# 09_CAN.net
KiCad netlist of a schematic drawn in Altium Designer
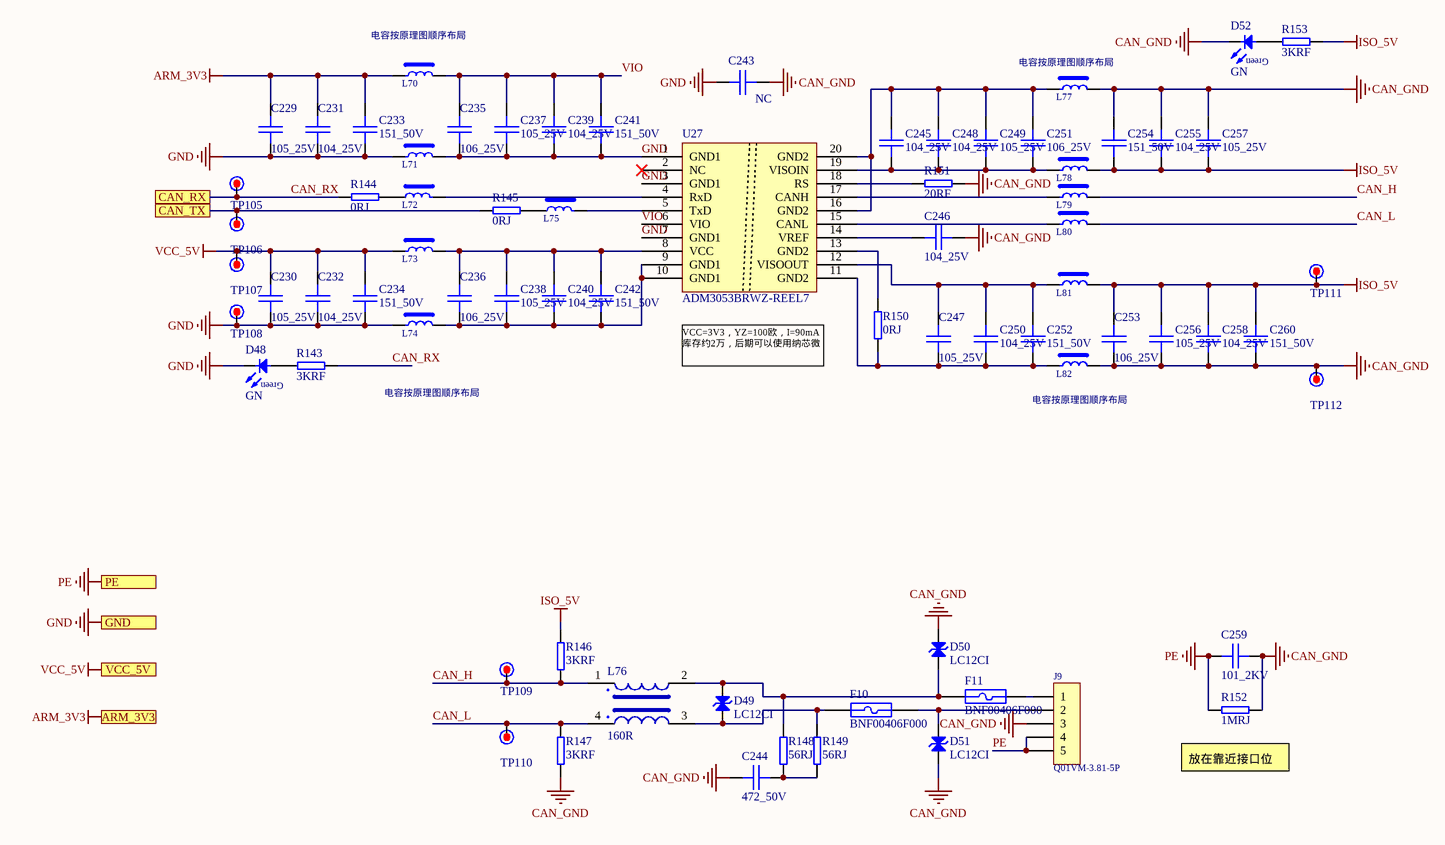
[diagram p0: 09_CAN.SchDoc]

(export (version "E")
  (design (tool "Eeschema 10.0.6"))
  (components
    (comp (ref "C229")
      (value "105_25V")
      (footprint "0603C")
      (description "贴片电容1uF25VX7R125℃K0603")
      (fields (field (name "检查人") "江应平"))
      (libsource (lib "NE Layout Library") (part "贴片电容1uF25VX7R125℃K0603"))
    )
    (comp (ref "C230")
      (value "105_25V")
      (footprint "0603C")
      (description "贴片电容1uF25VX7R125℃K0603")
      (fields (field (name "检查人") "江应平"))
      (libsource (lib "NE Layout Library") (part "贴片电容1uF25VX7R125℃K0603"))
    )
    (comp (ref "C231")
      (value "104_25V")
      (footprint "0402C")
      (description "贴片电容100nF25VX7R125℃K0402")
      (fields (field (name "检查人") "江应平"))
      (libsource (lib "NE Layout Library") (part "贴片电容100nF25VX7R125℃K0402"))
    )
    (comp (ref "C232")
      (value "104_25V")
      (footprint "0402C")
      (description "贴片电容100nF25VX7R125℃K0402")
      (fields (field (name "检查人") "江应平"))
      (libsource (lib "NE Layout Library") (part "贴片电容100nF25VX7R125℃K0402"))
    )
    (comp (ref "C233")
      (value "151_50V")
      (footprint "0603C")
      (description "贴片电容150pF50VCOG125℃K0603")
      (fields (field (name "检查人") "江应平"))
      (libsource (lib "NE Layout Library") (part "1102010037"))
    )
    (comp (ref "C234")
      (value "151_50V")
      (footprint "0603C")
      (description "贴片电容150pF50VCOG125℃K0603")
      (fields (field (name "检查人") "江应平"))
      (libsource (lib "NE Layout Library") (part "1102010037"))
    )
    (comp (ref "C235")
      (value "106_25V")
      (footprint "0805C")
      (description "贴片电容10uF25VX7R125℃K0805")
      (fields (field (name "检查人") "江应平"))
      (libsource (lib "NE Layout Library") (part "贴片电容10uF25VX7R125℃K0805"))
    )
    (comp (ref "C236")
      (value "106_25V")
      (footprint "0805C")
      (description "贴片电容10uF25VX7R125℃K0805")
      (fields (field (name "检查人") "江应平"))
      (libsource (lib "NE Layout Library") (part "贴片电容10uF25VX7R125℃K0805"))
    )
    (comp (ref "C237")
      (value "105_25V")
      (footprint "0603C")
      (description "贴片电容1uF25VX7R125℃K0603")
      (fields (field (name "检查人") "江应平"))
      (libsource (lib "NE Layout Library") (part "贴片电容1uF25VX7R125℃K0603"))
    )
    (comp (ref "C238")
      (value "105_25V")
      (footprint "0603C")
      (description "贴片电容1uF25VX7R125℃K0603")
      (fields (field (name "检查人") "江应平"))
      (libsource (lib "NE Layout Library") (part "贴片电容1uF25VX7R125℃K0603"))
    )
    (comp (ref "C239")
      (value "104_25V")
      (footprint "0603C")
      (description "贴片电容100nF25VX7R125℃K0603")
      (fields (field (name "检查人") "江应平"))
      (libsource (lib "NE Layout Library") (part "1102010026"))
    )
    (comp (ref "C240")
      (value "104_25V")
      (footprint "0603C")
      (description "贴片电容100nF25VX7R125℃K0603")
      (fields (field (name "检查人") "江应平"))
      (libsource (lib "NE Layout Library") (part "1102010026"))
    )
    (comp (ref "C241")
      (value "151_50V")
      (footprint "0603C")
      (description "贴片电容150pF50VCOG125℃K0603")
      (fields (field (name "检查人") "江应平"))
      (libsource (lib "NE Layout Library") (part "1102010037"))
    )
    (comp (ref "C242")
      (value "151_50V")
      (footprint "0603C")
      (description "贴片电容150pF50VCOG125℃K0603")
      (fields (field (name "检查人") "江应平"))
      (libsource (lib "NE Layout Library") (part "1102010037"))
    )
    (comp (ref "C243")
      (value "NC")
      (footprint "SMDC_L11.4W6H2.5")
      (libsource (lib "NE BufferLibrary0616") (part "电容DK1E3EA102M86RAH01"))
    )
    (comp (ref "C244")
      (value "472_50V")
      (footprint "0603C")
      (description "贴片电容4.7nF50VX7R125℃K0603")
      (fields (field (name "检查人") "江应平"))
      (libsource (lib "NE Layout Library") (part "1102010080"))
    )
    (comp (ref "C245")
      (value "104_25V")
      (footprint "0603C")
      (description "贴片电容100nF25VX7R125℃K0603")
      (fields (field (name "检查人") "江应平"))
      (libsource (lib "NE Layout Library") (part "1102010026"))
    )
    (comp (ref "C246")
      (value "104_25V")
      (footprint "0603C")
      (description "贴片电容100nF25VX7R125℃K0603")
      (fields (field (name "检查人") "江应平"))
      (libsource (lib "NE Layout Library") (part "1102010026"))
    )
    (comp (ref "C247")
      (value "105_25V")
      (footprint "0603C")
      (description "贴片电容1uF25VX7R125℃K0603")
      (fields (field (name "检查人") "江应平"))
      (libsource (lib "NE Layout Library") (part "贴片电容1uF25VX7R125℃K0603"))
    )
    (comp (ref "C248")
      (value "104_25V")
      (footprint "0603C")
      (description "贴片电容100nF25VX7R125℃K0603")
      (fields (field (name "检查人") "江应平"))
      (libsource (lib "NE Layout Library") (part "1102010026"))
    )
    (comp (ref "C249")
      (value "105_25V")
      (footprint "0603C")
      (description "贴片电容1uF25VX7R125℃K0603")
      (fields (field (name "检查人") "江应平"))
      (libsource (lib "NE Layout Library") (part "贴片电容1uF25VX7R125℃K0603"))
    )
    (comp (ref "C250")
      (value "104_25V")
      (footprint "0603C")
      (description "贴片电容100nF25VX7R125℃K0603")
      (fields (field (name "检查人") "江应平"))
      (libsource (lib "NE Layout Library") (part "1102010026"))
    )
    (comp (ref "C251")
      (value "106_25V")
      (footprint "0805C")
      (description "贴片电容10uF25VX7R125℃K0805")
      (fields (field (name "检查人") "江应平"))
      (libsource (lib "NE Layout Library") (part "贴片电容10uF25VX7R125℃K0805"))
    )
    (comp (ref "C252")
      (value "151_50V")
      (footprint "0603C")
      (description "贴片电容150pF50VCOG125℃K0603")
      (fields (field (name "检查人") "江应平"))
      (libsource (lib "NE Layout Library") (part "1102010037"))
    )
    (comp (ref "C253")
      (value "106_25V")
      (footprint "0805C")
      (description "贴片电容10uF25VX7R125℃K0805")
      (fields (field (name "检查人") "江应平"))
      (libsource (lib "NE Layout Library") (part "贴片电容10uF25VX7R125℃K0805"))
    )
    (comp (ref "C254")
      (value "151_50V")
      (footprint "0603C")
      (description "贴片电容150pF50VCOG125℃K0603")
      (fields (field (name "检查人") "江应平"))
      (libsource (lib "NE Layout Library") (part "1102010037"))
    )
    (comp (ref "C255")
      (value "104_25V")
      (footprint "0603C")
      (description "贴片电容100nF25VX7R125℃K0603")
      (fields (field (name "检查人") "江应平"))
      (libsource (lib "NE Layout Library") (part "1102010026"))
    )
    (comp (ref "C256")
      (value "105_25V")
      (footprint "0603C")
      (description "贴片电容1uF25VX7R125℃K0603")
      (fields (field (name "检查人") "江应平"))
      (libsource (lib "NE Layout Library") (part "贴片电容1uF25VX7R125℃K0603"))
    )
    (comp (ref "C257")
      (value "105_25V")
      (footprint "0603C")
      (description "贴片电容1uF25VX7R125℃K0603")
      (fields (field (name "检查人") "江应平"))
      (libsource (lib "NE Layout Library") (part "贴片电容1uF25VX7R125℃K0603"))
    )
    (comp (ref "C258")
      (value "104_25V")
      (footprint "0603C")
      (description "贴片电容100nF25VX7R125℃K0603")
      (fields (field (name "检查人") "江应平"))
      (libsource (lib "NE Layout Library") (part "1102010026"))
    )
    (comp (ref "C259")
      (value "101_2KV")
      (footprint "1812C")
      (description "贴片电容100pF2000VNPO125℃K1812")
      (fields (field (name "检查人") "江应平"))
      (libsource (lib "NE Layout Library") (part "1102010145"))
    )
    (comp (ref "C260")
      (value "151_50V")
      (footprint "0603C")
      (description "贴片电容150pF50VCOG125℃K0603")
      (fields (field (name "检查人") "江应平"))
      (libsource (lib "NE Layout Library") (part "1102010037"))
    )
    (comp (ref "D48")
      (value "GN")
      (footprint "SMDD_0603G")
      (description "贴片发光二极管GN0603")
      (fields (field (name "检查人") "江应平"))
      (libsource (lib "NE Layout Library") (part "贴片发光二极管GN0603"))
    )
    (comp (ref "D49")
      (value "LC12CI")
      (footprint "SMDD_SOD323(无极性)")
      (libsource (lib "NE BufferLibrary0916") (part "瞬态抑制二极管(TVS)LC12CI"))
    )
    (comp (ref "D50")
      (value "LC12CI")
      (footprint "SMDD_SOD323(无极性)")
      (libsource (lib "NE BufferLibrary0916") (part "瞬态抑制二极管(TVS)LC12CI"))
    )
    (comp (ref "D51")
      (value "LC12CI")
      (footprint "SMDD_SOD323(无极性)")
      (libsource (lib "NE BufferLibrary0916") (part "瞬态抑制二极管(TVS)LC12CI"))
    )
    (comp (ref "D52")
      (value "GN")
      (footprint "SMDD_0603G")
      (description "贴片发光二极管GN0603")
      (fields (field (name "检查人") "江应平"))
      (libsource (lib "NE Layout Library") (part "贴片发光二极管GN0603"))
    )
    (comp (ref "F10")
      (value "BNF00406F000")
      (footprint "SMDF_0603")
      (description "自恢复保险丝BNF00406F0000603")
      (fields (field (name "检查人") "江应平"))
      (libsource (lib "NE Layout Library") (part "1115000150"))
    )
    (comp (ref "F11")
      (value "BNF00406F000")
      (footprint "SMDF_0603")
      (description "自恢复保险丝BNF00406F0000603")
      (fields (field (name "检查人") "江应平"))
      (libsource (lib "NE Layout Library") (part "1115000150"))
    )
    (comp (ref "J9")
      (value "Q01VM-3.81-5P")
      (footprint "DIPJS_Q01VM_S3.81R0.8_5P")
      (description "连接座Q01VM-3.81-5P250V7A")
      (libsource (lib "NE Layout Library") (part "1214020289"))
    )
    (comp (ref "L70")
      (value "1.8K")
      (footprint "0402L")
      (description "贴片磁珠1.8K200mA100MHzL0402")
      (fields (field (name "检查人") "江应平"))
      (libsource (lib "NE Layout Library") (part "1111100012"))
    )
    (comp (ref "L71")
      (value "1.8K")
      (footprint "0402L")
      (description "贴片磁珠1.8K200mA100MHzL0402")
      (fields (field (name "检查人") "江应平"))
      (libsource (lib "NE Layout Library") (part "1111100012"))
    )
    (comp (ref "L72")
      (value "1.8K")
      (footprint "0402L")
      (description "贴片磁珠1.8K200mA100MHzL0402")
      (fields (field (name "检查人") "江应平"))
      (libsource (lib "") (part "1111100012_1"))
    )
    (comp (ref "L73")
      (value "1.8K")
      (footprint "0402L")
      (description "贴片磁珠1.8K200mA100MHzL0402")
      (fields (field (name "检查人") "江应平"))
      (libsource (lib "NE Layout Library") (part "1111100012"))
    )
    (comp (ref "L74")
      (value "1.8K")
      (footprint "0402L")
      (description "贴片磁珠1.8K200mA100MHzL0402")
      (fields (field (name "检查人") "江应平"))
      (libsource (lib "NE Layout Library") (part "1111100012"))
    )
    (comp (ref "L75")
      (value "1.8K")
      (footprint "0402L")
      (description "贴片磁珠1.8K200mA100MHzL0402")
      (fields (field (name "检查人") "江应平"))
      (libsource (lib "") (part "1111100012_1"))
    )
    (comp (ref "L76")
      (value "160R")
      (footprint "SMDL_L3.2W1.6_H1.8")
      (description "贴片共模电感160R0.34A125V1MHzSMD1206")
      (fields (field (name "检查人") "江应平"))
      (libsource (lib "NE Layout Library") (part "1111010051"))
    )
    (comp (ref "L77")
      (value "1.8K")
      (footprint "0402L")
      (description "贴片磁珠1.8K200mA100MHzL0402")
      (fields (field (name "检查人") "江应平"))
      (libsource (lib "NE Layout Library") (part "1111100012"))
    )
    (comp (ref "L78")
      (value "1.8K")
      (footprint "0402L")
      (description "贴片磁珠1.8K200mA100MHzL0402")
      (fields (field (name "检查人") "江应平"))
      (libsource (lib "NE Layout Library") (part "1111100012"))
    )
    (comp (ref "L79")
      (value "1.8K")
      (footprint "0402L")
      (description "贴片磁珠1.8K200mA100MHzL0402")
      (fields (field (name "检查人") "江应平"))
      (libsource (lib "NE Layout Library") (part "1111100012"))
    )
    (comp (ref "L80")
      (value "1.8K")
      (footprint "0402L")
      (description "贴片磁珠1.8K200mA100MHzL0402")
      (fields (field (name "检查人") "江应平"))
      (libsource (lib "NE Layout Library") (part "1111100012"))
    )
    (comp (ref "L81")
      (value "1.8K")
      (footprint "0402L")
      (description "贴片磁珠1.8K200mA100MHzL0402")
      (fields (field (name "检查人") "江应平"))
      (libsource (lib "NE Layout Library") (part "1111100012"))
    )
    (comp (ref "L82")
      (value "1.8K")
      (footprint "0402L")
      (description "贴片磁珠1.8K200mA100MHzL0402")
      (fields (field (name "检查人") "江应平"))
      (libsource (lib "NE Layout Library") (part "1111100012"))
    )
    (comp (ref "R143")
      (value "3KRF")
      (footprint "0603R")
      (description "贴片电阻3KRF0.1W100ppm0603")
      (fields (field (name "检查人") "江应平"))
      (libsource (lib "NE Layout Library") (part "贴片电阻3KRF0.1W100ppm0603"))
    )
    (comp (ref "R144")
      (value "0RJ")
      (footprint "0402R")
      (description "贴片电阻0RJ0.0625W100ppm0402")
      (fields (field (name "检查人") "江应平"))
      (libsource (lib "NE Layout Library") (part "1101010535"))
    )
    (comp (ref "R145")
      (value "0RJ")
      (footprint "0402R")
      (description "贴片电阻0RJ0.0625W100ppm0402")
      (fields (field (name "检查人") "江应平"))
      (libsource (lib "NE Layout Library") (part "1101010535"))
    )
    (comp (ref "R146")
      (value "3KRF")
      (footprint "0603R")
      (description "贴片电阻3KRF0.1W100ppm0603")
      (fields (field (name "检查人") "江应平"))
      (libsource (lib "NE Layout Library") (part "1101010254"))
    )
    (comp (ref "R147")
      (value "3KRF")
      (footprint "0603R")
      (description "贴片电阻3KRF0.1W100ppm0603")
      (fields (field (name "检查人") "江应平"))
      (libsource (lib "NE Layout Library") (part "1101010254"))
    )
    (comp (ref "R148")
      (value "56RJ")
      (footprint "0805R")
      (description "贴片电阻56RJ0.125W100ppm0805")
      (fields (field (name "检查人") "江应平"))
      (libsource (lib "NE Layout Library") (part "1101010179"))
    )
    (comp (ref "R149")
      (value "56RJ")
      (footprint "0805R")
      (description "贴片电阻56RJ0.125W100ppm0805")
      (fields (field (name "检查人") "江应平"))
      (libsource (lib "NE Layout Library") (part "1101010179"))
    )
    (comp (ref "R150")
      (value "0RJ")
      (footprint "0603R")
      (description "贴片电阻0RJ0.1W0603")
      (fields (field (name "检查人") "江应平"))
      (libsource (lib "NE Layout Library") (part "1101010220"))
    )
    (comp (ref "R151")
      (value "20RF")
      (footprint "0603R")
      (description "贴片电阻20RF0.1W100ppm0603")
      (fields (field (name "检查人") "江应平"))
      (libsource (lib "NE Layout Library") (part "1101010274"))
    )
    (comp (ref "R152")
      (value "1MRJ")
      (footprint "2512R")
      (description "贴片电阻1MRJ1W100ppm2512")
      (fields (field (name "检查人") "江应平"))
      (libsource (lib "NE Layout Library") (part "1101010313"))
    )
    (comp (ref "R153")
      (value "3KRF")
      (footprint "0603R")
      (description "贴片电阻3KRF0.1W100ppm0603")
      (fields (field (name "检查人") "江应平"))
      (libsource (lib "NE Layout Library") (part "贴片电阻3KRF0.1W100ppm0603"))
    )
    (comp (ref "TP105")
      (value "TP")
      (footprint "TP-1.0mm")
      (description "通用测试点")
      (libsource (lib "NE Layout Library") (part "TP"))
    )
    (comp (ref "TP106")
      (value "TP")
      (footprint "TP-1.0mm")
      (description "通用测试点")
      (libsource (lib "NE Layout Library") (part "TP"))
    )
    (comp (ref "TP107")
      (value "TP")
      (footprint "TP-1.0mm")
      (description "通用测试点")
      (libsource (lib "NE Layout Library") (part "TP"))
    )
    (comp (ref "TP108")
      (value "TP")
      (footprint "TP-1.0mm")
      (description "通用测试点")
      (libsource (lib "NE Layout Library") (part "TP"))
    )
    (comp (ref "TP109")
      (value "TP")
      (footprint "TP-1.0mm")
      (description "通用测试点")
      (libsource (lib "NE Layout Library") (part "TP"))
    )
    (comp (ref "TP110")
      (value "TP")
      (footprint "TP-1.0mm")
      (description "通用测试点")
      (libsource (lib "NE Layout Library") (part "TP"))
    )
    (comp (ref "TP111")
      (value "TP")
      (footprint "TP-1.0mm")
      (description "通用测试点")
      (libsource (lib "NE Layout Library") (part "TP"))
    )
    (comp (ref "TP112")
      (value "TP")
      (footprint "TP-1.0mm")
      (description "通用测试点")
      (libsource (lib "NE Layout Library") (part "TP"))
    )
    (comp (ref "U27")
      (value "ADM3053BRWZ-REEL7")
      (footprint "SMDU_SOP20-L_S1.27X10")
      (description "隔离通信芯片ADM3053BRWZ-REEL7RW-20")
      (fields (field (name "检查人") "江应平"))
      (libsource (lib "NE Layout Library") (part "1110080014"))
    )
  )
  (nets
    (net (code "1") (name "/CAN_H") (class "Default")
      (node (ref "L76") (pin "1") (pinfunction "1_1") (pintype "passive"))
      (node (ref "L79") (pin "1") (pinfunction "1_1") (pintype "passive"))
      (node (ref "R146") (pin "1") (pinfunction "1_1") (pintype "passive"))
      (node (ref "TP109") (pin "1") (pinfunction "1_1") (pintype "passive"))
    )
    (net (code "2") (name "/CAN_L") (class "Default")
      (node (ref "L76") (pin "4") (pinfunction "4_4") (pintype "passive"))
      (node (ref "L80") (pin "1") (pinfunction "1_1") (pintype "passive"))
      (node (ref "R147") (pin "2") (pinfunction "2_2") (pintype "passive"))
      (node (ref "TP110") (pin "1") (pinfunction "1_1") (pintype "passive"))
    )
    (net (code "3") (name "/CAN_RX") (class "Default")
      (node (ref "R143") (pin "1") (pinfunction "1_1") (pintype "passive"))
      (node (ref "R144") (pin "2") (pinfunction "2_2") (pintype "passive"))
      (node (ref "TP105") (pin "1") (pinfunction "1_1") (pintype "passive"))
    )
    (net (code "4") (name "/CAN_TX") (class "Default")
      (node (ref "R145") (pin "2") (pinfunction "2_2") (pintype "passive"))
      (node (ref "TP106") (pin "1") (pinfunction "1_1") (pintype "passive"))
    )
    (net (code "5") (name "/VIO") (class "Default")
      (node (ref "C235") (pin "1") (pinfunction "1_1") (pintype "passive"))
      (node (ref "C237") (pin "1") (pinfunction "1_1") (pintype "passive"))
      (node (ref "C239") (pin "1") (pinfunction "1_1") (pintype "passive"))
      (node (ref "C241") (pin "1") (pinfunction "1_1") (pintype "passive"))
      (node (ref "L70") (pin "1") (pinfunction "1_1") (pintype "passive"))
      (node (ref "U27") (pin "6") (pinfunction "VIO_6") (pintype "passive"))
    )
    (net (code "6") (name "ARM_3V3") (class "Default")
      (node (ref "C229") (pin "1") (pinfunction "1_1") (pintype "passive"))
      (node (ref "C231") (pin "1") (pinfunction "1_1") (pintype "passive"))
      (node (ref "C233") (pin "1") (pinfunction "1_1") (pintype "passive"))
      (node (ref "L70") (pin "2") (pinfunction "2_2") (pintype "passive"))
    )
    (net (code "7") (name "CAN_GND") (class "Default")
      (node (ref "C243") (pin "2") (pinfunction "2_2") (pintype "passive"))
      (node (ref "C244") (pin "1") (pinfunction "1_1") (pintype "passive"))
      (node (ref "C246") (pin "2") (pinfunction "2_2") (pintype "passive"))
      (node (ref "C253") (pin "2") (pinfunction "2_2") (pintype "passive"))
      (node (ref "C254") (pin "1") (pinfunction "1_1") (pintype "passive"))
      (node (ref "C255") (pin "1") (pinfunction "1_1") (pintype "passive"))
      (node (ref "C256") (pin "2") (pinfunction "2_2") (pintype "passive"))
      (node (ref "C257") (pin "1") (pinfunction "1_1") (pintype "passive"))
      (node (ref "C258") (pin "2") (pinfunction "2_2") (pintype "passive"))
      (node (ref "C259") (pin "2") (pinfunction "2_2") (pintype "passive"))
      (node (ref "C260") (pin "2") (pinfunction "2_2") (pintype "passive"))
      (node (ref "D50") (pin "2") (pinfunction "Pin2_2") (pintype "passive"))
      (node (ref "D51") (pin "1") (pinfunction "Pin1_1") (pintype "passive"))
      (node (ref "D52") (pin "2") (pinfunction "K_2") (pintype "passive"))
      (node (ref "J9") (pin "3") (pinfunction "3_3") (pintype "passive"))
      (node (ref "L77") (pin "1") (pinfunction "1_1") (pintype "passive"))
      (node (ref "L82") (pin "1") (pinfunction "1_1") (pintype "passive"))
      (node (ref "R147") (pin "1") (pinfunction "1_1") (pintype "passive"))
      (node (ref "R151") (pin "2") (pinfunction "2_2") (pintype "passive"))
      (node (ref "R152") (pin "2") (pinfunction "2_2") (pintype "passive"))
      (node (ref "TP112") (pin "1") (pinfunction "1_1") (pintype "passive"))
    )
    (net (code "8") (name "GND") (class "Default")
      (node (ref "C229") (pin "2") (pinfunction "2_2") (pintype "passive"))
      (node (ref "C230") (pin "2") (pinfunction "2_2") (pintype "passive"))
      (node (ref "C231") (pin "2") (pinfunction "2_2") (pintype "passive"))
      (node (ref "C232") (pin "2") (pinfunction "2_2") (pintype "passive"))
      (node (ref "C233") (pin "2") (pinfunction "2_2") (pintype "passive"))
      (node (ref "C234") (pin "2") (pinfunction "2_2") (pintype "passive"))
      (node (ref "C235") (pin "2") (pinfunction "2_2") (pintype "passive"))
      (node (ref "C237") (pin "2") (pinfunction "2_2") (pintype "passive"))
      (node (ref "C239") (pin "2") (pinfunction "2_2") (pintype "passive"))
      (node (ref "C241") (pin "2") (pinfunction "2_2") (pintype "passive"))
      (node (ref "C243") (pin "1") (pinfunction "1_1") (pintype "passive"))
      (node (ref "D48") (pin "2") (pinfunction "K_2") (pintype "passive"))
      (node (ref "L71") (pin "1") (pinfunction "1_1") (pintype "passive"))
      (node (ref "L71") (pin "2") (pinfunction "2_2") (pintype "passive"))
      (node (ref "L74") (pin "2") (pinfunction "2_2") (pintype "passive"))
      (node (ref "TP108") (pin "1") (pinfunction "1_1") (pintype "passive"))
      (node (ref "U27") (pin "1") (pinfunction "GND1_1") (pintype "passive"))
      (node (ref "U27") (pin "3") (pinfunction "GND1_3") (pintype "passive"))
      (node (ref "U27") (pin "7") (pinfunction "GND1_7") (pintype "passive"))
    )
    (net (code "9") (name "ISO_5V") (class "Default")
      (node (ref "C253") (pin "1") (pinfunction "1_1") (pintype "passive"))
      (node (ref "C254") (pin "2") (pinfunction "2_2") (pintype "passive"))
      (node (ref "C255") (pin "2") (pinfunction "2_2") (pintype "passive"))
      (node (ref "C256") (pin "1") (pinfunction "1_1") (pintype "passive"))
      (node (ref "C257") (pin "2") (pinfunction "2_2") (pintype "passive"))
      (node (ref "C258") (pin "1") (pinfunction "1_1") (pintype "passive"))
      (node (ref "C260") (pin "1") (pinfunction "1_1") (pintype "passive"))
      (node (ref "L78") (pin "1") (pinfunction "1_1") (pintype "passive"))
      (node (ref "L81") (pin "1") (pinfunction "1_1") (pintype "passive"))
      (node (ref "R146") (pin "2") (pinfunction "2_2") (pintype "passive"))
      (node (ref "R153") (pin "1") (pinfunction "1_1") (pintype "passive"))
      (node (ref "TP111") (pin "1") (pinfunction "1_1") (pintype "passive"))
    )
    (net (code "10") (name "Net-(C236-Pad2)") (class "Default")
      (node (ref "C236") (pin "2") (pinfunction "2_2") (pintype "passive"))
      (node (ref "C238") (pin "2") (pinfunction "2_2") (pintype "passive"))
      (node (ref "C240") (pin "2") (pinfunction "2_2") (pintype "passive"))
      (node (ref "C242") (pin "2") (pinfunction "2_2") (pintype "passive"))
      (node (ref "L74") (pin "1") (pinfunction "1_1") (pintype "passive"))
      (node (ref "U27") (pin "10") (pinfunction "GND1_10") (pintype "passive"))
      (node (ref "U27") (pin "9") (pinfunction "GND1_9") (pintype "passive"))
    )
    (net (code "11") (name "Net-(C244-Pad2)") (class "Default")
      (node (ref "C244") (pin "2") (pinfunction "2_2") (pintype "passive"))
      (node (ref "R148") (pin "1") (pinfunction "1_1") (pintype "passive"))
      (node (ref "R149") (pin "1") (pinfunction "1_1") (pintype "passive"))
    )
    (net (code "12") (name "Net-(C245-Pad1)") (class "Default")
      (node (ref "C245") (pin "1") (pinfunction "1_1") (pintype "passive"))
      (node (ref "C248") (pin "1") (pinfunction "1_1") (pintype "passive"))
      (node (ref "C249") (pin "1") (pinfunction "1_1") (pintype "passive"))
      (node (ref "C251") (pin "1") (pinfunction "1_1") (pintype "passive"))
      (node (ref "L77") (pin "2") (pinfunction "2_2") (pintype "passive"))
      (node (ref "U27") (pin "16") (pinfunction "GND2_16") (pintype "passive"))
      (node (ref "U27") (pin "20") (pinfunction "GND2_20") (pintype "passive"))
    )
    (net (code "13") (name "Net-(C247-Pad2)") (class "Default")
      (node (ref "C247") (pin "2") (pinfunction "2_2") (pintype "passive"))
      (node (ref "C250") (pin "2") (pinfunction "2_2") (pintype "passive"))
      (node (ref "C252") (pin "2") (pinfunction "2_2") (pintype "passive"))
      (node (ref "L82") (pin "2") (pinfunction "2_2") (pintype "passive"))
      (node (ref "R150") (pin "1") (pinfunction "1_1") (pintype "passive"))
      (node (ref "U27") (pin "11") (pinfunction "GND2_11") (pintype "passive"))
    )
    (net (code "14") (name "Net-(D48-A)") (class "Default")
      (node (ref "D48") (pin "1") (pinfunction "A_1") (pintype "passive"))
      (node (ref "R143") (pin "2") (pinfunction "2_2") (pintype "passive"))
    )
    (net (code "15") (name "Net-(D49-Pin1)") (class "Default")
      (node (ref "D49") (pin "1") (pinfunction "Pin1_1") (pintype "passive"))
      (node (ref "F10") (pin "1") (pinfunction "1_1") (pintype "passive"))
      (node (ref "L76") (pin "3") (pinfunction "3_3") (pintype "passive"))
      (node (ref "R149") (pin "2") (pinfunction "2_2") (pintype "passive"))
    )
    (net (code "16") (name "Net-(D49-Pin2)") (class "Default")
      (node (ref "D49") (pin "2") (pinfunction "Pin2_2") (pintype "passive"))
      (node (ref "D50") (pin "1") (pinfunction "Pin1_1") (pintype "passive"))
      (node (ref "F11") (pin "1") (pinfunction "1_1") (pintype "passive"))
      (node (ref "L76") (pin "2") (pinfunction "2_2") (pintype "passive"))
      (node (ref "R148") (pin "2") (pinfunction "2_2") (pintype "passive"))
    )
    (net (code "17") (name "Net-(D51-Pin2)") (class "Default")
      (node (ref "D51") (pin "2") (pinfunction "Pin2_2") (pintype "passive"))
      (node (ref "F10") (pin "2") (pinfunction "2_2") (pintype "passive"))
      (node (ref "J9") (pin "2") (pinfunction "2_2") (pintype "passive"))
    )
    (net (code "18") (name "Net-(D52-A)") (class "Default")
      (node (ref "D52") (pin "1") (pinfunction "A_1") (pintype "passive"))
      (node (ref "R153") (pin "2") (pinfunction "2_2") (pintype "passive"))
    )
    (net (code "19") (name "Net-(F11-Pad2)") (class "Default")
      (node (ref "F11") (pin "2") (pinfunction "2_2") (pintype "passive"))
      (node (ref "J9") (pin "1") (pinfunction "1_1") (pintype "passive"))
    )
    (net (code "20") (name "Net-(L72-Pad1)") (class "Default")
      (node (ref "L72") (pin "1") (pinfunction "1_1") (pintype "passive"))
      (node (ref "R144") (pin "1") (pinfunction "1_1") (pintype "passive"))
    )
    (net (code "21") (name "Net-(L75-Pad1)") (class "Default")
      (node (ref "L75") (pin "1") (pinfunction "1_1") (pintype "passive"))
      (node (ref "R145") (pin "1") (pinfunction "1_1") (pintype "passive"))
    )
    (net (code "22") (name "Net-(R150-Pad2)") (class "Default")
      (node (ref "R150") (pin "2") (pinfunction "2_2") (pintype "passive"))
      (node (ref "U27") (pin "13") (pinfunction "GND2_13") (pintype "passive"))
    )
    (net (code "23") (name "Net-(U27-CANH)") (class "Default")
      (node (ref "L79") (pin "2") (pinfunction "2_2") (pintype "passive"))
      (node (ref "U27") (pin "17") (pinfunction "CANH_17") (pintype "passive"))
    )
    (net (code "24") (name "Net-(U27-CANL)") (class "Default")
      (node (ref "L80") (pin "2") (pinfunction "2_2") (pintype "passive"))
      (node (ref "U27") (pin "15") (pinfunction "CANL_15") (pintype "passive"))
    )
    (net (code "25") (name "Net-(U27-RS)") (class "Default")
      (node (ref "R151") (pin "1") (pinfunction "1_1") (pintype "passive"))
      (node (ref "U27") (pin "18") (pinfunction "RS_18") (pintype "passive"))
    )
    (net (code "26") (name "Net-(U27-RxD)") (class "Default")
      (node (ref "L72") (pin "2") (pinfunction "2_2") (pintype "passive"))
      (node (ref "U27") (pin "4") (pinfunction "RxD_4") (pintype "passive"))
    )
    (net (code "27") (name "Net-(U27-TxD)") (class "Default")
      (node (ref "L75") (pin "2") (pinfunction "2_2") (pintype "passive"))
      (node (ref "U27") (pin "5") (pinfunction "TxD_5") (pintype "passive"))
    )
    (net (code "28") (name "Net-(U27-VCC)") (class "Default")
      (node (ref "C236") (pin "1") (pinfunction "1_1") (pintype "passive"))
      (node (ref "C238") (pin "1") (pinfunction "1_1") (pintype "passive"))
      (node (ref "C240") (pin "1") (pinfunction "1_1") (pintype "passive"))
      (node (ref "C242") (pin "1") (pinfunction "1_1") (pintype "passive"))
      (node (ref "L73") (pin "1") (pinfunction "1_1") (pintype "passive"))
      (node (ref "U27") (pin "8") (pinfunction "VCC_8") (pintype "passive"))
    )
    (net (code "29") (name "Net-(U27-VISOIN)") (class "Default")
      (node (ref "C245") (pin "2") (pinfunction "2_2") (pintype "passive"))
      (node (ref "C248") (pin "2") (pinfunction "2_2") (pintype "passive"))
      (node (ref "C249") (pin "2") (pinfunction "2_2") (pintype "passive"))
      (node (ref "C251") (pin "2") (pinfunction "2_2") (pintype "passive"))
      (node (ref "L78") (pin "2") (pinfunction "2_2") (pintype "passive"))
      (node (ref "U27") (pin "19") (pinfunction "VISOIN_19") (pintype "passive"))
    )
    (net (code "30") (name "Net-(U27-VISOOUT)") (class "Default")
      (node (ref "C247") (pin "1") (pinfunction "1_1") (pintype "passive"))
      (node (ref "C250") (pin "1") (pinfunction "1_1") (pintype "passive"))
      (node (ref "C252") (pin "1") (pinfunction "1_1") (pintype "passive"))
      (node (ref "L81") (pin "2") (pinfunction "2_2") (pintype "passive"))
      (node (ref "U27") (pin "12") (pinfunction "VISOOUT_12") (pintype "passive"))
    )
    (net (code "31") (name "Net-(U27-VREF)") (class "Default")
      (node (ref "C246") (pin "1") (pinfunction "1_1") (pintype "passive"))
      (node (ref "U27") (pin "14") (pinfunction "VREF_14") (pintype "passive"))
    )
    (net (code "32") (name "PE") (class "Default")
      (node (ref "C259") (pin "1") (pinfunction "1_1") (pintype "passive"))
      (node (ref "J9") (pin "4") (pinfunction "4_4") (pintype "passive"))
      (node (ref "J9") (pin "5") (pinfunction "5_5") (pintype "passive"))
      (node (ref "R152") (pin "1") (pinfunction "1_1") (pintype "passive"))
    )
    (net (code "33") (name "VCC_5V") (class "Default")
      (node (ref "C230") (pin "1") (pinfunction "1_1") (pintype "passive"))
      (node (ref "C232") (pin "1") (pinfunction "1_1") (pintype "passive"))
      (node (ref "C234") (pin "1") (pinfunction "1_1") (pintype "passive"))
      (node (ref "L73") (pin "2") (pinfunction "2_2") (pintype "passive"))
      (node (ref "TP107") (pin "1") (pinfunction "1_1") (pintype "passive"))
    )
    (net (code "34") (name "unconnected-(U27-NC-Pad2)") (class "Default")
      (node (ref "U27") (pin "2") (pinfunction "NC_2") (pintype "passive+no_connect"))
    )
  )
)
